# ftdi_rev_3.net
KiCad netlist of a schematic drawn in EAGLE
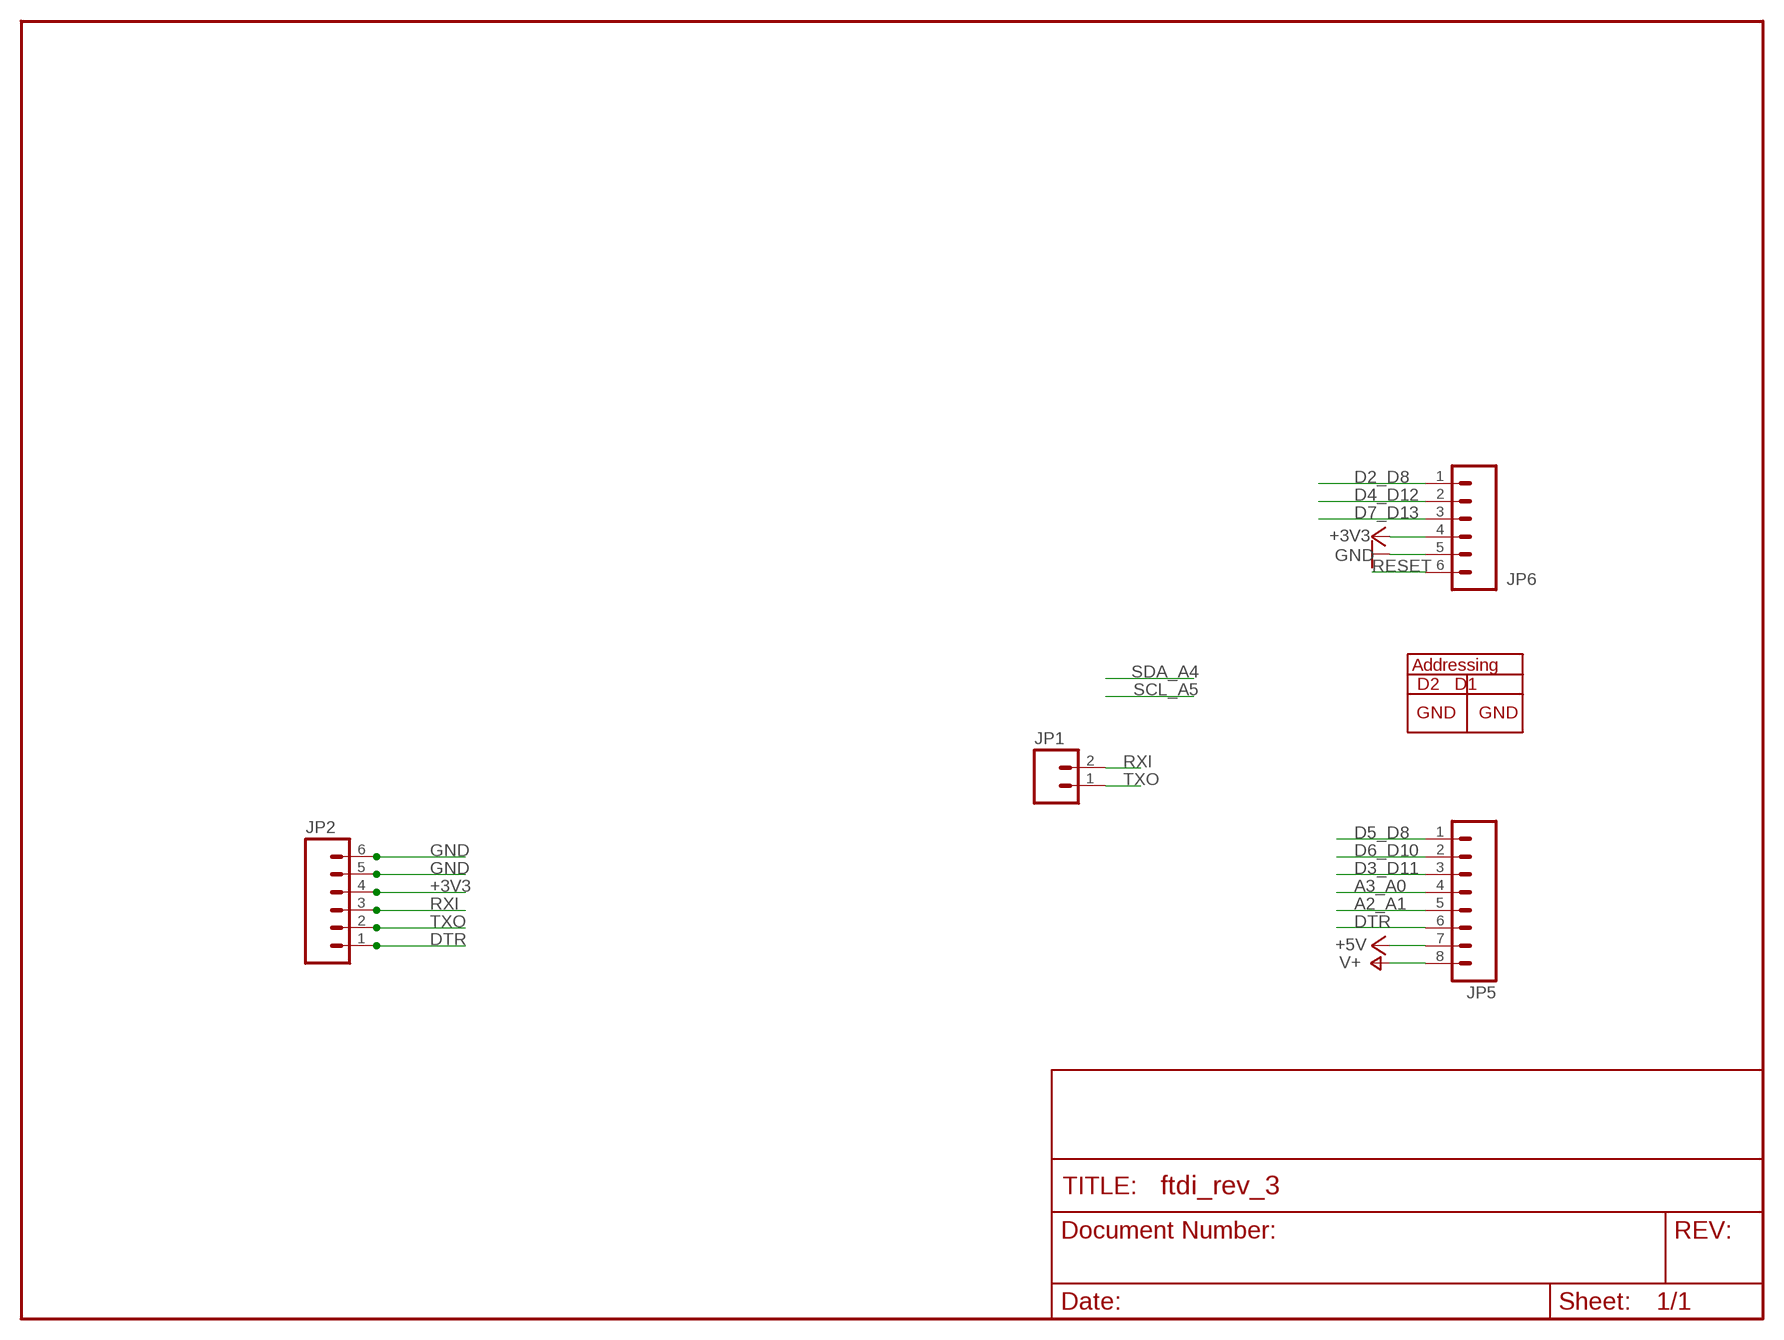
[diagram p0: schematic, sheet 1]

(export (version "E")
  (design (tool "Eeschema 10.0.6"))
  (components
    (comp (ref "JP1")
      (value "M02PTH")
      (footprint "eagle-import:1X02")
      (libsource (lib "eagle-import") (part "M02PTH"))
    )
    (comp (ref "JP2")
      (value "M06SIP")
      (footprint "eagle-import:1X06")
      (libsource (lib "eagle-import") (part "SparkFun_mod_M06SIP"))
    )
    (comp (ref "JP5")
      (value "M081X08")
      (footprint "eagle-import:1X08")
      (libsource (lib "eagle-import") (part "M081X08"))
    )
    (comp (ref "JP6")
      (value "M06SIP")
      (footprint "eagle-import:1X06")
      (libsource (lib "eagle-import") (part "M06SIP"))
    )
  )
  (nets
    (net (code "1") (name "+3V3") (class "Default")
      (node (ref "JP2") (pin "4") (pinfunction "4_4") (pintype "passive"))
      (node (ref "JP6") (pin "4") (pinfunction "4_4") (pintype "passive"))
    )
    (net (code "2") (name "+5V") (class "Default")
      (node (ref "JP5") (pin "7") (pinfunction "7_7") (pintype "passive"))
    )
    (net (code "3") (name "/A2_A1") (class "Default")
      (node (ref "JP5") (pin "5") (pinfunction "5_5") (pintype "passive"))
    )
    (net (code "4") (name "/A3_A0") (class "Default")
      (node (ref "JP5") (pin "4") (pinfunction "4_4") (pintype "passive"))
    )
    (net (code "5") (name "/D2_D8") (class "Default")
      (node (ref "JP6") (pin "1") (pinfunction "1_1") (pintype "passive"))
    )
    (net (code "6") (name "/D3_D11") (class "Default")
      (node (ref "JP5") (pin "3") (pinfunction "3_3") (pintype "passive"))
    )
    (net (code "7") (name "/D4_D12") (class "Default")
      (node (ref "JP6") (pin "2") (pinfunction "2_2") (pintype "passive"))
    )
    (net (code "8") (name "/D5_D8") (class "Default")
      (node (ref "JP5") (pin "1") (pinfunction "1_1") (pintype "passive"))
    )
    (net (code "9") (name "/D6_D10") (class "Default")
      (node (ref "JP5") (pin "2") (pinfunction "2_2") (pintype "passive"))
    )
    (net (code "10") (name "/D7_D13") (class "Default")
      (node (ref "JP6") (pin "3") (pinfunction "3_3") (pintype "passive"))
    )
    (net (code "11") (name "/DTR") (class "Default")
      (node (ref "JP2") (pin "1") (pinfunction "1_1") (pintype "passive"))
      (node (ref "JP5") (pin "6") (pinfunction "6_6") (pintype "passive"))
    )
    (net (code "12") (name "/RESET") (class "Default")
      (node (ref "JP6") (pin "6") (pinfunction "6_6") (pintype "passive"))
    )
    (net (code "13") (name "/RXI") (class "Default")
      (node (ref "JP1") (pin "2") (pinfunction "2_2") (pintype "passive"))
      (node (ref "JP2") (pin "3") (pinfunction "3_3") (pintype "passive"))
    )
    (net (code "16") (name "/TXO") (class "Default")
      (node (ref "JP1") (pin "1") (pinfunction "1_1") (pintype "passive"))
      (node (ref "JP2") (pin "2") (pinfunction "2_2") (pintype "passive"))
    )
    (net (code "17") (name "GND") (class "Default")
      (node (ref "JP2") (pin "5") (pinfunction "5_5") (pintype "passive"))
      (node (ref "JP2") (pin "6") (pinfunction "6_6") (pintype "passive"))
      (node (ref "JP6") (pin "5") (pinfunction "5_5") (pintype "passive"))
    )
    (net (code "18") (name "V+") (class "Default")
      (node (ref "JP5") (pin "8") (pinfunction "8_8") (pintype "passive"))
    )
  )
)
